# MCU.net
KiCad netlist of a schematic drawn in Altium Designer
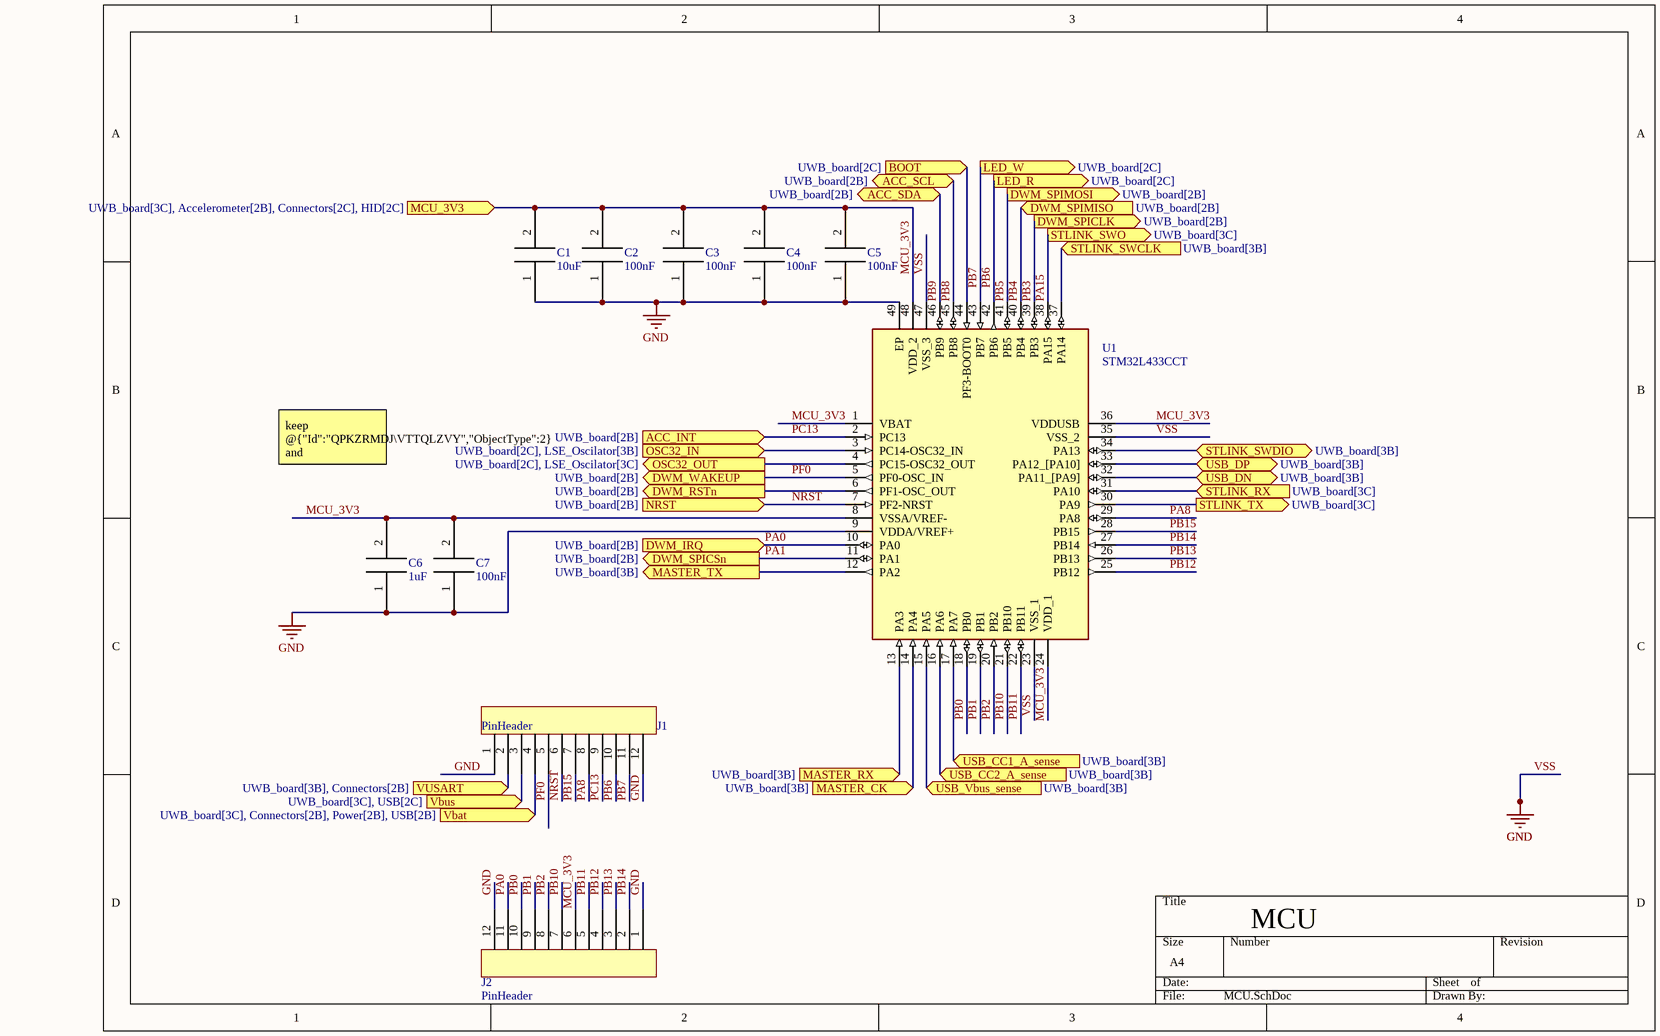
[diagram p0: MCU.SchDoc]

(export (version "E")
  (design (tool "Eeschema 10.0.6"))
  (components
    (comp (ref "C1")
      (value "10uF")
      (footprint "0603_cap")
      (description "100nF 50V X7R ±10% 0603 Multilayer Ceramic Capacitors MLCC - SMD/SMT ROHS")
      (fields (field (name "LCSC PART #") "C19702"))
      (libsource (lib "Schlib1") (part "CL10A106KP8NNNC"))
    )
    (comp (ref "C2")
      (value "100nF")
      (footprint "0603_cap")
      (description "100nF 50V X7R ±10% 0603 Multilayer Ceramic Capacitors MLCC - SMD/SMT ROHS")
      (fields (field (name "LCSC PART #") "C14663"))
      (libsource (lib "Schlib1") (part "CC0603KRX7R9BB104"))
    )
    (comp (ref "C3")
      (value "100nF")
      (footprint "0603_cap")
      (description "100nF 50V X7R ±10% 0603 Multilayer Ceramic Capacitors MLCC - SMD/SMT ROHS")
      (fields (field (name "LCSC PART #") "C14663"))
      (libsource (lib "Schlib1") (part "CC0603KRX7R9BB104"))
    )
    (comp (ref "C4")
      (value "100nF")
      (footprint "0603_cap")
      (description "100nF 50V X7R ±10% 0603 Multilayer Ceramic Capacitors MLCC - SMD/SMT ROHS")
      (fields (field (name "LCSC PART #") "C14663"))
      (libsource (lib "Schlib1") (part "CC0603KRX7R9BB104"))
    )
    (comp (ref "C5")
      (value "100nF")
      (footprint "0603_cap")
      (description "100nF 50V X7R ±10% 0603 Multilayer Ceramic Capacitors MLCC - SMD/SMT ROHS")
      (fields (field (name "LCSC PART #") "C14663"))
      (libsource (lib "Schlib1") (part "CC0603KRX7R9BB104"))
    )
    (comp (ref "C6")
      (value "1uF")
      (footprint "0603_cap")
      (description "1uF 50V X5R ±10% 0603 Multilayer Ceramic Capacitors MLCC - SMD/SMT ROHS")
      (fields (field (name "LCSC PART #") "C15849"))
      (libsource (lib "Schlib1") (part "CL10A105KB8NNNC"))
    )
    (comp (ref "C7")
      (value "100nF")
      (footprint "0603_cap")
      (description "100nF 50V X7R ±10% 0603 Multilayer Ceramic Capacitors MLCC - SMD/SMT ROHS")
      (fields (field (name "LCSC PART #") "C14663"))
      (libsource (lib "Schlib1") (part "CC0603KRX7R9BB104"))
    )
    (comp (ref "J1") (value "PinHeader") (footprint "PINs") (libsource (lib "") (part "PinHeader_1")))
    (comp (ref "J2") (value "PinHeader") (footprint "PINs") (libsource (lib "Schlib1") (part "PinHeader")))
    (comp (ref "U1")
      (value "STM32L433CCT")
      (footprint "LQFP50")
      (libsource (lib "Schlib1") (part "STM32L433CCT"))
    )
  )
  (nets
    (net (code "1") (name "/BOOT") (class "Default")
      (node (ref "U1") (pin "44") (pinfunction "PF3-BOOT0_44") (pintype "input"))
    )
    (net (code "2") (name "/DWM_RSTn") (class "Default")
      (node (ref "U1") (pin "6") (pinfunction "PF1-OSC_OUT_6") (pintype "output"))
    )
    (net (code "3") (name "/MASTER_CK") (class "Default")
      (node (ref "U1") (pin "14") (pinfunction "PA4_14") (pintype "input"))
    )
    (net (code "4") (name "/MASTER_RX") (class "Default")
      (node (ref "U1") (pin "13") (pinfunction "PA3_13") (pintype "input"))
    )
    (net (code "5") (name "/MASTER_TX") (class "Default")
      (node (ref "U1") (pin "12") (pinfunction "PA2_12") (pintype "output"))
    )
    (net (code "6") (name "/MCU_3V3") (class "Default")
      (node (ref "C1") (pin "2") (pinfunction "3_2") (pintype "passive"))
      (node (ref "C2") (pin "2") (pinfunction "3_2") (pintype "passive"))
      (node (ref "C3") (pin "2") (pinfunction "3_2") (pintype "passive"))
      (node (ref "C4") (pin "2") (pinfunction "3_2") (pintype "passive"))
      (node (ref "C5") (pin "2") (pinfunction "3_2") (pintype "passive"))
      (node (ref "C6") (pin "2") (pinfunction "3_2") (pintype "passive"))
      (node (ref "C7") (pin "2") (pinfunction "3_2") (pintype "passive"))
      (node (ref "J2") (pin "6") (pintype "passive"))
      (node (ref "U1") (pin "1") (pinfunction "VBAT_1") (pintype "passive"))
      (node (ref "U1") (pin "24") (pinfunction "VDD_1_24") (pintype "passive"))
      (node (ref "U1") (pin "36") (pinfunction "VDDUSB_36") (pintype "passive"))
      (node (ref "U1") (pin "48") (pinfunction "VDD_2_48") (pintype "passive"))
      (node (ref "U1") (pin "8") (pinfunction "VSSA/VREF-_8") (pintype "passive"))
    )
    (net (code "7") (name "/NRST") (class "Default")
      (node (ref "J1") (pin "6") (pintype "passive"))
      (node (ref "U1") (pin "7") (pinfunction "PF2-NRST_7") (pintype "input"))
    )
    (net (code "8") (name "/OSC32_IN") (class "Default")
      (node (ref "U1") (pin "3") (pinfunction "PC14-OSC32_IN_3") (pintype "input"))
    )
    (net (code "9") (name "/OSC32_OUT") (class "Default")
      (node (ref "U1") (pin "4") (pinfunction "PC15-OSC32_OUT_4") (pintype "output"))
    )
    (net (code "10") (name "/PA0") (class "Default")
      (node (ref "J2") (pin "11") (pintype "passive"))
      (node (ref "U1") (pin "10") (pinfunction "PA0_10") (pintype "bidirectional"))
    )
    (net (code "11") (name "/PA1") (class "Default")
      (node (ref "U1") (pin "11") (pinfunction "PA1_11") (pintype "bidirectional"))
    )
    (net (code "12") (name "/PA8") (class "Default")
      (node (ref "J1") (pin "8") (pintype "passive"))
      (node (ref "U1") (pin "29") (pinfunction "PA8_29") (pintype "bidirectional"))
    )
    (net (code "13") (name "/PA15") (class "Default")
      (node (ref "U1") (pin "38") (pinfunction "PA15_38") (pintype "bidirectional"))
    )
    (net (code "14") (name "/PB0") (class "Default")
      (node (ref "J2") (pin "10") (pintype "passive"))
      (node (ref "U1") (pin "18") (pinfunction "PB0_18") (pintype "bidirectional"))
    )
    (net (code "15") (name "/PB1") (class "Default")
      (node (ref "J2") (pin "9") (pintype "passive"))
      (node (ref "U1") (pin "19") (pinfunction "PB1_19") (pintype "bidirectional"))
    )
    (net (code "16") (name "/PB2") (class "Default")
      (node (ref "J2") (pin "8") (pintype "passive"))
      (node (ref "U1") (pin "20") (pinfunction "PB2_20") (pintype "input"))
    )
    (net (code "17") (name "/PB3") (class "Default")
      (node (ref "U1") (pin "39") (pinfunction "PB3_39") (pintype "bidirectional"))
    )
    (net (code "18") (name "/PB4") (class "Default")
      (node (ref "U1") (pin "40") (pinfunction "PB4_40") (pintype "bidirectional"))
    )
    (net (code "19") (name "/PB5") (class "Default")
      (node (ref "U1") (pin "41") (pinfunction "PB5_41") (pintype "bidirectional"))
    )
    (net (code "20") (name "/PB6") (class "Default")
      (node (ref "J1") (pin "10") (pintype "passive"))
      (node (ref "U1") (pin "42") (pinfunction "PB6_42") (pintype "output"))
    )
    (net (code "21") (name "/PB7") (class "Default")
      (node (ref "J1") (pin "11") (pintype "passive"))
      (node (ref "U1") (pin "43") (pinfunction "PB7_43") (pintype "input"))
    )
    (net (code "22") (name "/PB8") (class "Default")
      (node (ref "U1") (pin "45") (pinfunction "PB8_45") (pintype "bidirectional"))
    )
    (net (code "23") (name "/PB9") (class "Default")
      (node (ref "U1") (pin "46") (pinfunction "PB9_46") (pintype "bidirectional"))
    )
    (net (code "24") (name "/PB10") (class "Default")
      (node (ref "J2") (pin "7") (pintype "passive"))
      (node (ref "U1") (pin "21") (pinfunction "PB10_21") (pintype "bidirectional"))
    )
    (net (code "25") (name "/PB11") (class "Default")
      (node (ref "J2") (pin "5") (pintype "passive"))
      (node (ref "U1") (pin "22") (pinfunction "PB11_22") (pintype "bidirectional"))
    )
    (net (code "26") (name "/PB12") (class "Default")
      (node (ref "J2") (pin "4") (pintype "passive"))
      (node (ref "U1") (pin "25") (pinfunction "PB12_25") (pintype "output"))
    )
    (net (code "27") (name "/PB13") (class "Default")
      (node (ref "J2") (pin "3") (pintype "passive"))
      (node (ref "U1") (pin "26") (pinfunction "PB13_26") (pintype "output"))
    )
    (net (code "28") (name "/PB14") (class "Default")
      (node (ref "J2") (pin "2") (pintype "passive"))
      (node (ref "U1") (pin "27") (pinfunction "PB14_27") (pintype "input"))
    )
    (net (code "29") (name "/PB15") (class "Default")
      (node (ref "J1") (pin "7") (pintype "passive"))
      (node (ref "U1") (pin "28") (pinfunction "PB15_28") (pintype "output"))
    )
    (net (code "30") (name "/PC13") (class "Default")
      (node (ref "J1") (pin "9") (pintype "passive"))
      (node (ref "U1") (pin "2") (pinfunction "PC13_2") (pintype "input"))
    )
    (net (code "31") (name "/PF0") (class "Default")
      (node (ref "J1") (pin "5") (pintype "passive"))
      (node (ref "U1") (pin "5") (pinfunction "PF0-OSC_IN_5") (pintype "output"))
    )
    (net (code "32") (name "/STLINK_RX") (class "Default")
      (node (ref "U1") (pin "31") (pinfunction "PA10_31") (pintype "bidirectional"))
    )
    (net (code "33") (name "/STLINK_SWCLK") (class "Default")
      (node (ref "U1") (pin "37") (pinfunction "PA14_37") (pintype "bidirectional"))
    )
    (net (code "34") (name "/STLINK_SWDIO") (class "Default")
      (node (ref "U1") (pin "34") (pinfunction "PA13_34") (pintype "bidirectional"))
    )
    (net (code "35") (name "/STLINK_TX") (class "Default")
      (node (ref "U1") (pin "30") (pinfunction "PA9_30") (pintype "output"))
    )
    (net (code "36") (name "/USB_CC1_A_sense") (class "Default")
      (node (ref "U1") (pin "17") (pinfunction "PA7_17") (pintype "input"))
    )
    (net (code "37") (name "/USB_CC2_A_sense") (class "Default")
      (node (ref "U1") (pin "16") (pinfunction "PA6_16") (pintype "input"))
    )
    (net (code "38") (name "/USB_DN") (class "Default")
      (node (ref "U1") (pin "32") (pinfunction "PA11_[PA9]_32") (pintype "bidirectional"))
    )
    (net (code "39") (name "/USB_DP") (class "Default")
      (node (ref "U1") (pin "33") (pinfunction "PA12_[PA10]_33") (pintype "bidirectional"))
    )
    (net (code "40") (name "/USB_Vbus_sense") (class "Default")
      (node (ref "U1") (pin "15") (pinfunction "PA5_15") (pintype "input"))
    )
    (net (code "41") (name "/VUSART") (class "Default") (node (ref "J1") (pin "2") (pintype "passive")))
    (net (code "42") (name "/Vbat") (class "Default") (node (ref "J1") (pin "4") (pintype "passive")))
    (net (code "43") (name "/Vbus") (class "Default") (node (ref "J1") (pin "3") (pintype "passive")))
    (net (code "44") (name "GND") (class "Default")
      (node (ref "C1") (pin "1") (pintype "passive"))
      (node (ref "C2") (pin "1") (pintype "passive"))
      (node (ref "C3") (pin "1") (pintype "passive"))
      (node (ref "C4") (pin "1") (pintype "passive"))
      (node (ref "C5") (pin "1") (pintype "passive"))
      (node (ref "C6") (pin "1") (pintype "passive"))
      (node (ref "C7") (pin "1") (pintype "passive"))
      (node (ref "J1") (pin "1") (pintype "passive"))
      (node (ref "J1") (pin "12") (pintype "passive"))
      (node (ref "J2") (pin "1") (pintype "passive"))
      (node (ref "J2") (pin "12") (pintype "passive"))
      (node (ref "U1") (pin "23") (pinfunction "VSS_1_23") (pintype "passive"))
      (node (ref "U1") (pin "35") (pinfunction "VSS_2_35") (pintype "passive"))
      (node (ref "U1") (pin "47") (pinfunction "VSS_3_47") (pintype "passive"))
      (node (ref "U1") (pin "49") (pinfunction "EP_49") (pintype "passive"))
      (node (ref "U1") (pin "9") (pinfunction "VDDA/VREF+_9") (pintype "passive"))
    )
  )
)
